# relay_dip_v02.net
KiCad netlist of a schematic drawn in EAGLE
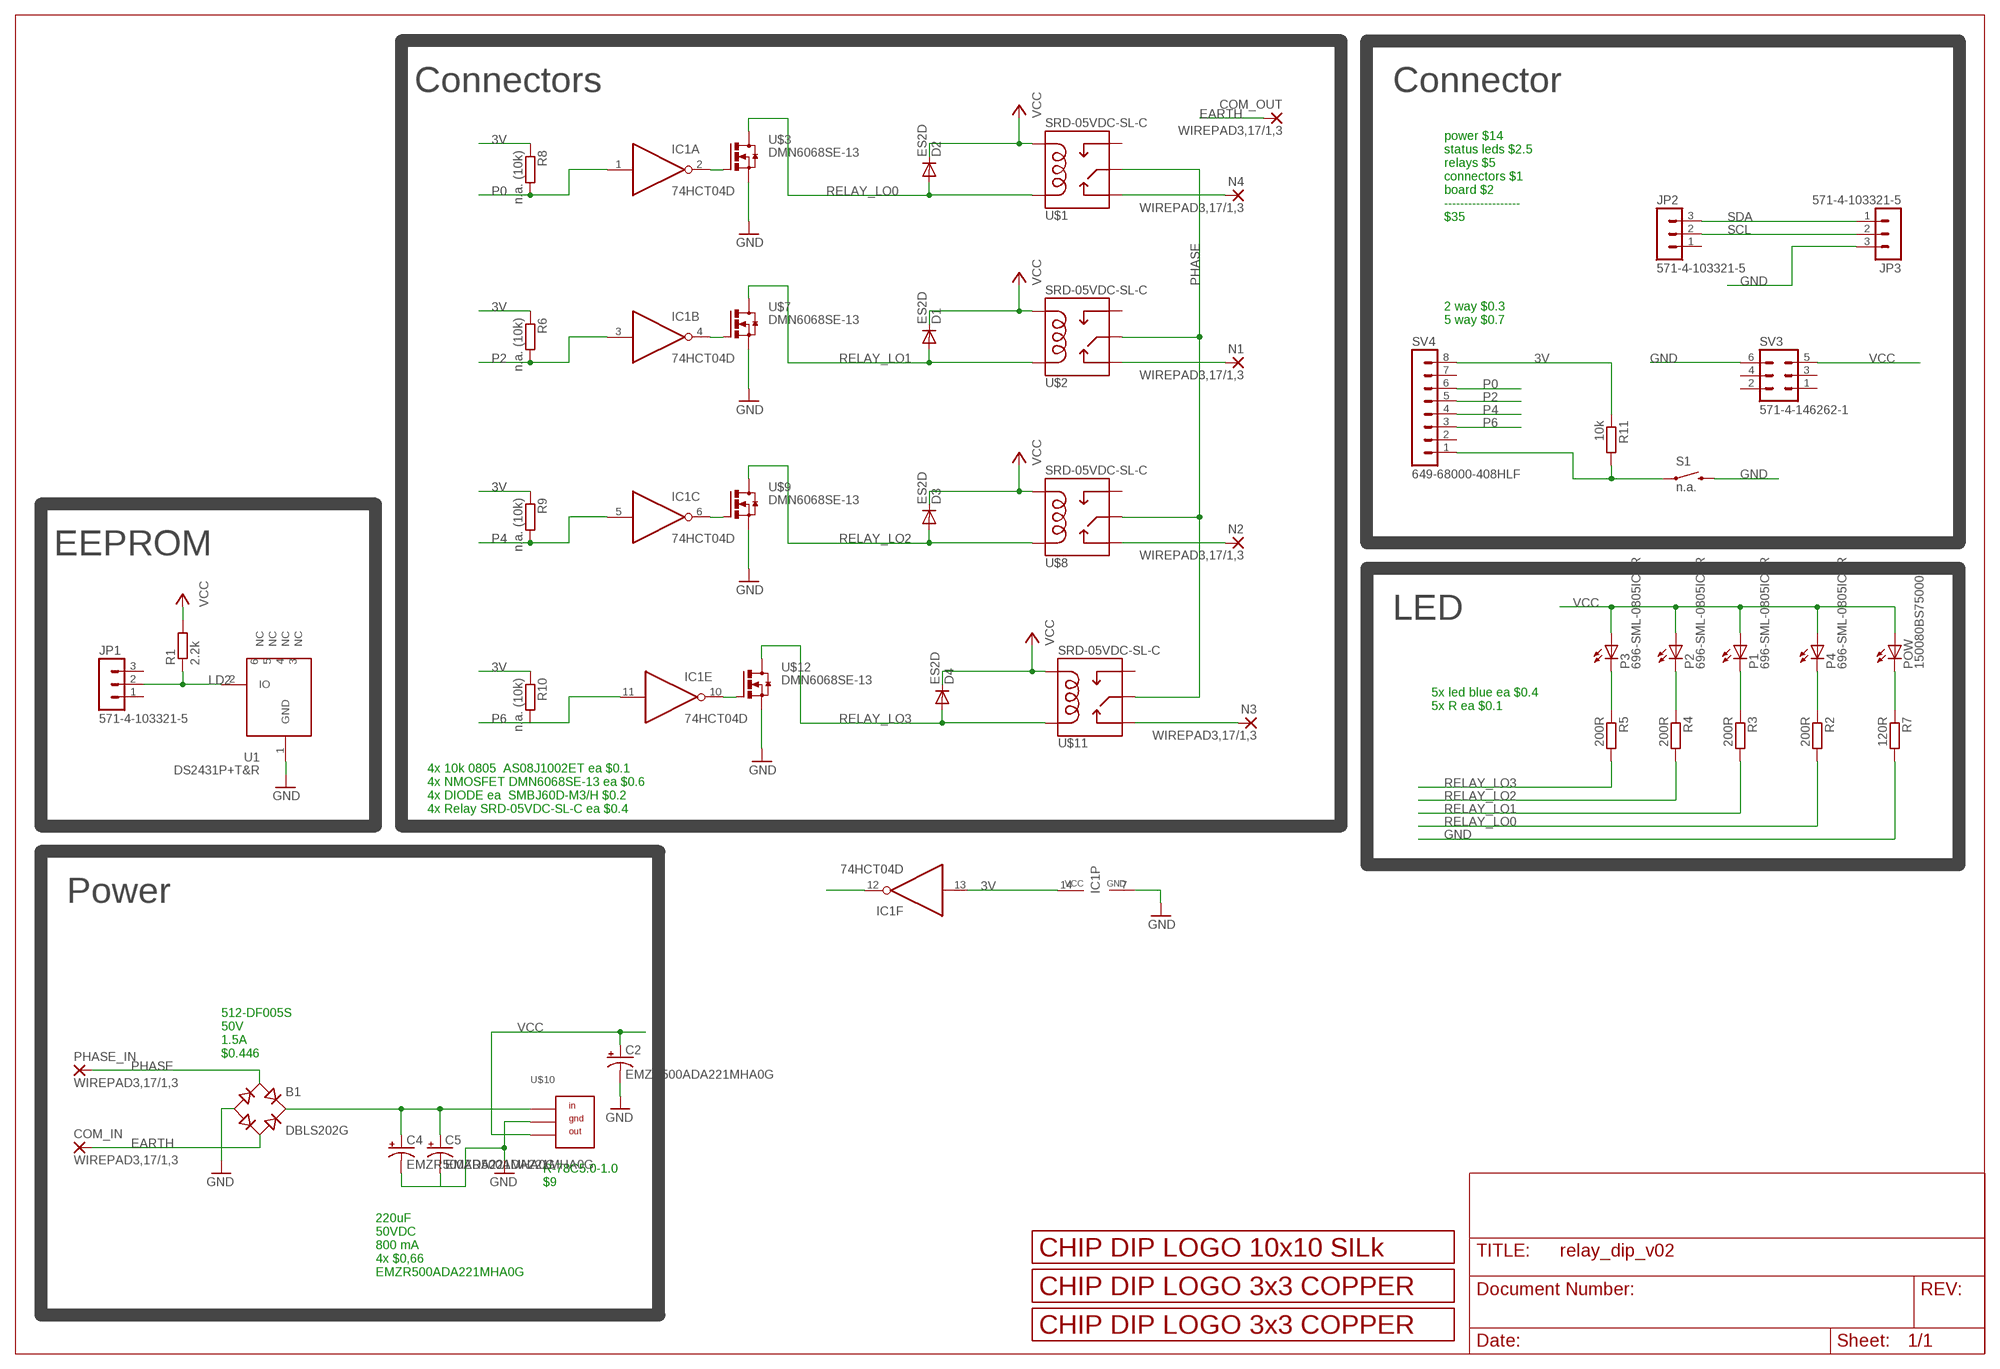
[diagram p0: schematic, sheet 1]

(export (version "E")
  (design (tool "Eeschema 10.0.6"))
  (components
    (comp (ref "B1")
      (value "DBLS202G")
      (footprint "eagle-import:DBS")
      (libsource (lib "eagle-import") (part "DB?GLS202"))
    )
    (comp (ref "C2")
      (value "EMZR500ADA221MHA0G")
      (footprint "eagle-import:150CLZ-0810")
      (libsource (lib "eagle-import") (part "CPOL-US150CLZ-0810"))
    )
    (comp (ref "C4")
      (value "EMZR500ADA221MHA0G")
      (footprint "eagle-import:150CLZ-0810")
      (libsource (lib "eagle-import") (part "CPOL-US150CLZ-0810"))
    )
    (comp (ref "C5")
      (value "EMZR500ADA221MHA0G")
      (footprint "eagle-import:150CLZ-0810")
      (libsource (lib "eagle-import") (part "CPOL-US150CLZ-0810"))
    )
    (comp (ref "COM_IN")
      (value "WIREPAD3,17/1,3")
      (footprint "eagle-import:3,17_1,3")
      (libsource (lib "eagle-import") (part "WIREPAD3,17/1,3"))
    )
    (comp (ref "COM_OUT")
      (value "WIREPAD3,17/1,3")
      (footprint "eagle-import:3,17_1,3")
      (libsource (lib "eagle-import") (part "WIREPAD3,17/1,3"))
    )
    (comp (ref "D1")
      (value "ES2D")
      (footprint "eagle-import:SMB")
      (libsource (lib "eagle-import") (part "DIODE-SMB"))
    )
    (comp (ref "D2")
      (value "ES2D")
      (footprint "eagle-import:SMB")
      (libsource (lib "eagle-import") (part "DIODE-SMB"))
    )
    (comp (ref "D3")
      (value "ES2D")
      (footprint "eagle-import:SMB")
      (libsource (lib "eagle-import") (part "DIODE-SMB"))
    )
    (comp (ref "D4")
      (value "ES2D")
      (footprint "eagle-import:SMB")
      (libsource (lib "eagle-import") (part "DIODE-SMB"))
    )
    (comp (ref "IC1")
      (value "74HCT04D")
      (footprint "eagle-import:SO14")
      (libsource (lib "eagle-import") (part "7404DHCT"))
    )
    (comp (ref "JP1")
      (value "571-4-103321-5")
      (footprint "eagle-import:MA03-1")
      (libsource (lib "eagle-import") (part "MA03-1"))
    )
    (comp (ref "JP2")
      (value "571-4-103321-5")
      (footprint "eagle-import:MA03-1")
      (libsource (lib "eagle-import") (part "MA03-1"))
    )
    (comp (ref "JP3")
      (value "571-4-103321-5")
      (footprint "eagle-import:MA03-1")
      (libsource (lib "eagle-import") (part "MA03-1"))
    )
    (comp (ref "N1")
      (value "WIREPAD3,17/1,3")
      (footprint "eagle-import:3,17_1,3")
      (libsource (lib "eagle-import") (part "WIREPAD3,17/1,3"))
    )
    (comp (ref "N2")
      (value "WIREPAD3,17/1,3")
      (footprint "eagle-import:3,17_1,3")
      (libsource (lib "eagle-import") (part "WIREPAD3,17/1,3"))
    )
    (comp (ref "N3")
      (value "WIREPAD3,17/1,3")
      (footprint "eagle-import:3,17_1,3")
      (libsource (lib "eagle-import") (part "WIREPAD3,17/1,3"))
    )
    (comp (ref "N4")
      (value "WIREPAD3,17/1,3")
      (footprint "eagle-import:3,17_1,3")
      (libsource (lib "eagle-import") (part "WIREPAD3,17/1,3"))
    )
    (comp (ref "P1")
      (value "696-SML-0805ICTR")
      (footprint "eagle-import:CHIP-LED0805")
      (libsource (lib "eagle-import") (part "LEDCHIP-LED0805"))
    )
    (comp (ref "P2")
      (value "696-SML-0805ICTR")
      (footprint "eagle-import:CHIP-LED0805")
      (libsource (lib "eagle-import") (part "LEDCHIP-LED0805"))
    )
    (comp (ref "P3")
      (value "696-SML-0805ICTR")
      (footprint "eagle-import:CHIP-LED0805")
      (libsource (lib "eagle-import") (part "LEDCHIP-LED0805"))
    )
    (comp (ref "P4")
      (value "696-SML-0805ICTR")
      (footprint "eagle-import:CHIP-LED0805")
      (libsource (lib "eagle-import") (part "LEDCHIP-LED0805"))
    )
    (comp (ref "PHASE_IN")
      (value "WIREPAD3,17/1,3")
      (footprint "eagle-import:3,17_1,3")
      (libsource (lib "eagle-import") (part "WIREPAD3,17/1,3"))
    )
    (comp (ref "POW")
      (value "150080BS75000")
      (footprint "eagle-import:CHIP-LED0805")
      (libsource (lib "eagle-import") (part "LEDCHIP-LED0805"))
    )
    (comp (ref "R1")
      (value "2.2k")
      (footprint "eagle-import:R0805")
      (libsource (lib "eagle-import") (part "R-EU_R0805"))
    )
    (comp (ref "R2")
      (value "200R")
      (footprint "eagle-import:R0805")
      (libsource (lib "eagle-import") (part "R-EU_R0805"))
    )
    (comp (ref "R3")
      (value "200R")
      (footprint "eagle-import:R0805")
      (libsource (lib "eagle-import") (part "R-EU_R0805"))
    )
    (comp (ref "R4")
      (value "200R")
      (footprint "eagle-import:R0805")
      (libsource (lib "eagle-import") (part "R-EU_R0805"))
    )
    (comp (ref "R5")
      (value "200R")
      (footprint "eagle-import:R0805")
      (libsource (lib "eagle-import") (part "R-EU_R0805"))
    )
    (comp (ref "R6")
      (value "n.a. (10k)")
      (footprint "eagle-import:R0805")
      (libsource (lib "eagle-import") (part "R-EU_R0805"))
    )
    (comp (ref "R7")
      (value "120R")
      (footprint "eagle-import:R0805")
      (libsource (lib "eagle-import") (part "R-EU_R0805"))
    )
    (comp (ref "R8")
      (value "n.a. (10k)")
      (footprint "eagle-import:R0805")
      (libsource (lib "eagle-import") (part "R-EU_R0805"))
    )
    (comp (ref "R9")
      (value "n.a. (10k)")
      (footprint "eagle-import:R0805")
      (libsource (lib "eagle-import") (part "R-EU_R0805"))
    )
    (comp (ref "R10")
      (value "n.a. (10k)")
      (footprint "eagle-import:R0805")
      (libsource (lib "eagle-import") (part "R-EU_R0805"))
    )
    (comp (ref "R11")
      (value "10k")
      (footprint "eagle-import:R0805")
      (libsource (lib "eagle-import") (part "R-EU_R0805"))
    )
    (comp (ref "S1")
      (value "n.a.")
      (footprint "eagle-import:TACTILE-SWITCH-SMD")
      (libsource (lib "eagle-import") (part "SWITCH-MOMENTARY-2SMD"))
    )
    (comp (ref "SV3")
      (value "571-4-146262-1")
      (footprint "eagle-import:MA03-2")
      (libsource (lib "eagle-import") (part "MA03-2"))
    )
    (comp (ref "SV4")
      (value "649-68000-408HLF")
      (footprint "eagle-import:MA08-1")
      (libsource (lib "eagle-import") (part "MA08-1"))
    )
    (comp (ref "U$1")
      (value "SRD-05VDC-SL-C")
      (footprint "eagle-import:SRD-05VDC-SL-C")
      (libsource (lib "eagle-import") (part "RELAYPTH"))
    )
    (comp (ref "U$2")
      (value "SRD-05VDC-SL-C")
      (footprint "eagle-import:SRD-05VDC-SL-C")
      (libsource (lib "eagle-import") (part "RELAYPTH"))
    )
    (comp (ref "U$3")
      (value "DMN6068SE-13")
      (footprint "eagle-import:SOT223")
      (libsource (lib "eagle-import") (part "NMOSFET_SMD_223"))
    )
    (comp (ref "U$4")
      (value "LOGO_3X3_COPPER")
      (footprint "eagle-import:LOGO_3X3_COPPER")
      (libsource (lib "eagle-import") (part "LOGO_3X3_COPPER"))
    )
    (comp (ref "U$5")
      (value "LOGO_10X10_SILK")
      (footprint "eagle-import:LOGO_10X10_SILK")
      (libsource (lib "eagle-import") (part "LOGO_10X10_SILK"))
    )
    (comp (ref "U$6")
      (value "LOGO_3X3_COPPER")
      (footprint "eagle-import:LOGO_3X3_COPPER")
      (libsource (lib "eagle-import") (part "LOGO_3X3_COPPER"))
    )
    (comp (ref "U$7")
      (value "DMN6068SE-13")
      (footprint "eagle-import:SOT223")
      (libsource (lib "eagle-import") (part "NMOSFET_SMD_223"))
    )
    (comp (ref "U$8")
      (value "SRD-05VDC-SL-C")
      (footprint "eagle-import:SRD-05VDC-SL-C")
      (libsource (lib "eagle-import") (part "RELAYPTH"))
    )
    (comp (ref "U$9")
      (value "DMN6068SE-13")
      (footprint "eagle-import:SOT223")
      (libsource (lib "eagle-import") (part "NMOSFET_SMD_223"))
    )
    (comp (ref "U$10")
      (value "R-7805-1.0")
      (footprint "eagle-import:SIP3")
      (libsource (lib "eagle-import") (part "R-7805-1.0"))
    )
    (comp (ref "U$11")
      (value "SRD-05VDC-SL-C")
      (footprint "eagle-import:SRD-05VDC-SL-C")
      (libsource (lib "eagle-import") (part "RELAYPTH"))
    )
    (comp (ref "U$12")
      (value "DMN6068SE-13")
      (footprint "eagle-import:SOT223")
      (libsource (lib "eagle-import") (part "NMOSFET_SMD_223"))
    )
    (comp (ref "U1")
      (value "DS2431P+T&R")
      (footprint "eagle-import:TSOC6")
      (fields (field (name "MFG") "DIGIKEY"))
      (libsource (lib "eagle-import") (part "DS2431P"))
    )
  )
  (nets
    (net (code "1") (name "/3V") (class "Default")
      (node (ref "IC1") (pin "13") (pinfunction "I_13") (pintype "input"))
      (node (ref "IC1") (pin "14") (pinfunction "VCC_14") (pintype "power_in"))
      (node (ref "R10") (pin "1") (pinfunction "1_1") (pintype "passive"))
      (node (ref "R11") (pin "1") (pinfunction "1_1") (pintype "passive"))
      (node (ref "R6") (pin "1") (pinfunction "1_1") (pintype "passive"))
      (node (ref "R8") (pin "1") (pinfunction "1_1") (pintype "passive"))
      (node (ref "R9") (pin "1") (pinfunction "1_1") (pintype "passive"))
      (node (ref "SV4") (pin "8") (pinfunction "8_8") (pintype "passive"))
    )
    (net (code "2") (name "/EARTH") (class "Default")
      (node (ref "B1") (pin "AC2") (pinfunction "AC2_AC2") (pintype "passive"))
      (node (ref "COM_IN") (pin "1") (pinfunction "P_1") (pintype "passive"))
      (node (ref "COM_OUT") (pin "1") (pinfunction "P_1") (pintype "passive"))
    )
    (net (code "3") (name "/LD2") (class "Default")
      (node (ref "JP1") (pin "2") (pinfunction "2_2") (pintype "passive"))
      (node (ref "R1") (pin "1") (pinfunction "1_1") (pintype "passive"))
      (node (ref "U1") (pin "2") (pinfunction "IO_2") (pintype "bidirectional"))
    )
    (net (code "4") (name "/P0") (class "Default")
      (node (ref "IC1") (pin "1") (pinfunction "I_1") (pintype "input"))
      (node (ref "R8") (pin "2") (pinfunction "2_2") (pintype "passive"))
      (node (ref "SV4") (pin "6") (pinfunction "6_6") (pintype "passive"))
    )
    (net (code "5") (name "/P2") (class "Default")
      (node (ref "IC1") (pin "3") (pinfunction "I_3") (pintype "input"))
      (node (ref "R6") (pin "2") (pinfunction "2_2") (pintype "passive"))
      (node (ref "SV4") (pin "5") (pinfunction "5_5") (pintype "passive"))
    )
    (net (code "6") (name "/P4") (class "Default")
      (node (ref "IC1") (pin "5") (pinfunction "I_5") (pintype "input"))
      (node (ref "R9") (pin "2") (pinfunction "2_2") (pintype "passive"))
      (node (ref "SV4") (pin "4") (pinfunction "4_4") (pintype "passive"))
    )
    (net (code "7") (name "/P6") (class "Default")
      (node (ref "IC1") (pin "11") (pinfunction "I_11") (pintype "input"))
      (node (ref "R10") (pin "2") (pinfunction "2_2") (pintype "passive"))
      (node (ref "SV4") (pin "3") (pinfunction "3_3") (pintype "passive"))
    )
    (net (code "8") (name "/PHASE") (class "Default")
      (node (ref "B1") (pin "AC1") (pinfunction "AC1_AC1") (pintype "passive"))
      (node (ref "PHASE_IN") (pin "1") (pinfunction "P_1") (pintype "passive"))
      (node (ref "U$1") (pin "SWCOMMON") (pinfunction "SWCOMMON_SWCOMMON") (pintype "bidirectional"))
      (node (ref "U$11") (pin "SWCOMMON") (pinfunction "SWCOMMON_SWCOMMON") (pintype "bidirectional"))
      (node (ref "U$2") (pin "SWCOMMON") (pinfunction "SWCOMMON_SWCOMMON") (pintype "bidirectional"))
      (node (ref "U$8") (pin "SWCOMMON") (pinfunction "SWCOMMON_SWCOMMON") (pintype "bidirectional"))
    )
    (net (code "9") (name "/RELAY_LO0") (class "Default")
      (node (ref "D2") (pin "A") (pinfunction "A_A") (pintype "passive"))
      (node (ref "R2") (pin "2") (pinfunction "2_2") (pintype "passive"))
      (node (ref "U$1") (pin "COIL1") (pinfunction "COIL1_COIL1") (pintype "bidirectional"))
      (node (ref "U$3") (pin "2") (pinfunction "D_2") (pintype "passive"))
      (node (ref "U$3") (pin "4") (pinfunction "D_4") (pintype "passive"))
    )
    (net (code "10") (name "/RELAY_LO1") (class "Default")
      (node (ref "D1") (pin "A") (pinfunction "A_A") (pintype "passive"))
      (node (ref "R3") (pin "2") (pinfunction "2_2") (pintype "passive"))
      (node (ref "U$2") (pin "COIL1") (pinfunction "COIL1_COIL1") (pintype "bidirectional"))
      (node (ref "U$7") (pin "2") (pinfunction "D_2") (pintype "passive"))
      (node (ref "U$7") (pin "4") (pinfunction "D_4") (pintype "passive"))
    )
    (net (code "11") (name "/RELAY_LO2") (class "Default")
      (node (ref "D3") (pin "A") (pinfunction "A_A") (pintype "passive"))
      (node (ref "R4") (pin "2") (pinfunction "2_2") (pintype "passive"))
      (node (ref "U$8") (pin "COIL1") (pinfunction "COIL1_COIL1") (pintype "bidirectional"))
      (node (ref "U$9") (pin "2") (pinfunction "D_2") (pintype "passive"))
      (node (ref "U$9") (pin "4") (pinfunction "D_4") (pintype "passive"))
    )
    (net (code "12") (name "/RELAY_LO3") (class "Default")
      (node (ref "D4") (pin "A") (pinfunction "A_A") (pintype "passive"))
      (node (ref "R5") (pin "2") (pinfunction "2_2") (pintype "passive"))
      (node (ref "U$11") (pin "COIL1") (pinfunction "COIL1_COIL1") (pintype "bidirectional"))
      (node (ref "U$12") (pin "2") (pinfunction "D_2") (pintype "passive"))
      (node (ref "U$12") (pin "4") (pinfunction "D_4") (pintype "passive"))
    )
    (net (code "13") (name "/SCL") (class "Default")
      (node (ref "JP2") (pin "2") (pinfunction "2_2") (pintype "passive"))
      (node (ref "JP3") (pin "2") (pinfunction "2_2") (pintype "passive"))
    )
    (net (code "14") (name "/SDA") (class "Default")
      (node (ref "JP2") (pin "3") (pinfunction "3_3") (pintype "passive"))
      (node (ref "JP3") (pin "1") (pinfunction "1_1") (pintype "passive"))
    )
    (net (code "15") (name "GND") (class "Default")
      (node (ref "B1") (pin "-") (pinfunction "-_-") (pintype "passive"))
      (node (ref "C2") (pin "-") (pinfunction "-_-") (pintype "passive"))
      (node (ref "C4") (pin "-") (pinfunction "-_-") (pintype "passive"))
      (node (ref "C5") (pin "-") (pinfunction "-_-") (pintype "passive"))
      (node (ref "IC1") (pin "7") (pinfunction "GND_7") (pintype "power_in"))
      (node (ref "JP3") (pin "3") (pinfunction "3_3") (pintype "passive"))
      (node (ref "R7") (pin "2") (pinfunction "2_2") (pintype "passive"))
      (node (ref "S1") (pin "3") (pinfunction "2_3") (pintype "passive"))
      (node (ref "SV3") (pin "6") (pinfunction "6_6") (pintype "passive"))
      (node (ref "U$10") (pin "GND") (pinfunction "GND_GND") (pintype "bidirectional"))
      (node (ref "U$12") (pin "3") (pinfunction "S_3") (pintype "passive"))
      (node (ref "U$3") (pin "3") (pinfunction "S_3") (pintype "passive"))
      (node (ref "U$7") (pin "3") (pinfunction "S_3") (pintype "passive"))
      (node (ref "U$9") (pin "3") (pinfunction "S_3") (pintype "passive"))
      (node (ref "U1") (pin "1") (pinfunction "GND_1") (pintype "bidirectional"))
    )
    (net (code "16") (name "Net-(B1-Pad+)") (class "Default")
      (node (ref "B1") (pin "+") (pinfunction "+_+") (pintype "passive"))
      (node (ref "C4") (pin "+") (pinfunction "+_+") (pintype "passive"))
      (node (ref "C5") (pin "+") (pinfunction "+_+") (pintype "passive"))
      (node (ref "U$10") (pin "IN") (pinfunction "IN_IN") (pintype "bidirectional"))
    )
    (net (code "17") (name "Net-(IC1A-O)") (class "Default")
      (node (ref "IC1") (pin "2") (pinfunction "O_2") (pintype "output"))
      (node (ref "U$3") (pin "1") (pinfunction "G_1") (pintype "passive"))
    )
    (net (code "18") (name "Net-(IC1B-O)") (class "Default")
      (node (ref "IC1") (pin "4") (pinfunction "O_4") (pintype "output"))
      (node (ref "U$7") (pin "1") (pinfunction "G_1") (pintype "passive"))
    )
    (net (code "19") (name "Net-(IC1C-O)") (class "Default")
      (node (ref "IC1") (pin "6") (pinfunction "O_6") (pintype "output"))
      (node (ref "U$9") (pin "1") (pinfunction "G_1") (pintype "passive"))
    )
    (net (code "20") (name "Net-(IC1E-O)") (class "Default")
      (node (ref "IC1") (pin "10") (pinfunction "O_10") (pintype "output"))
      (node (ref "U$12") (pin "1") (pinfunction "G_1") (pintype "passive"))
    )
    (net (code "21") (name "Net-(N1-P)") (class "Default")
      (node (ref "N1") (pin "1") (pinfunction "P_1") (pintype "passive"))
      (node (ref "U$2") (pin "SWCLOSED") (pinfunction "SWCLOSE_SWCLOSED") (pintype "bidirectional"))
    )
    (net (code "22") (name "Net-(N2-P)") (class "Default")
      (node (ref "N2") (pin "1") (pinfunction "P_1") (pintype "passive"))
      (node (ref "U$8") (pin "SWCLOSED") (pinfunction "SWCLOSE_SWCLOSED") (pintype "bidirectional"))
    )
    (net (code "23") (name "Net-(N3-P)") (class "Default")
      (node (ref "N3") (pin "1") (pinfunction "P_1") (pintype "passive"))
      (node (ref "U$11") (pin "SWCLOSED") (pinfunction "SWCLOSE_SWCLOSED") (pintype "bidirectional"))
    )
    (net (code "24") (name "Net-(N4-P)") (class "Default")
      (node (ref "N4") (pin "1") (pinfunction "P_1") (pintype "passive"))
      (node (ref "U$1") (pin "SWCLOSED") (pinfunction "SWCLOSE_SWCLOSED") (pintype "bidirectional"))
    )
    (net (code "25") (name "Net-(P1-PadC)") (class "Default")
      (node (ref "P1") (pin "C") (pinfunction "C_C") (pintype "passive"))
      (node (ref "R3") (pin "1") (pinfunction "1_1") (pintype "passive"))
    )
    (net (code "26") (name "Net-(P2-PadC)") (class "Default")
      (node (ref "P2") (pin "C") (pinfunction "C_C") (pintype "passive"))
      (node (ref "R4") (pin "1") (pinfunction "1_1") (pintype "passive"))
    )
    (net (code "27") (name "Net-(P3-PadC)") (class "Default")
      (node (ref "P3") (pin "C") (pinfunction "C_C") (pintype "passive"))
      (node (ref "R5") (pin "1") (pinfunction "1_1") (pintype "passive"))
    )
    (net (code "28") (name "Net-(P4-PadC)") (class "Default")
      (node (ref "P4") (pin "C") (pinfunction "C_C") (pintype "passive"))
      (node (ref "R2") (pin "1") (pinfunction "1_1") (pintype "passive"))
    )
    (net (code "29") (name "Net-(POW-PadC)") (class "Default")
      (node (ref "POW") (pin "C") (pinfunction "C_C") (pintype "passive"))
      (node (ref "R7") (pin "1") (pinfunction "1_1") (pintype "passive"))
    )
    (net (code "30") (name "Net-(R11-Pad2)") (class "Default")
      (node (ref "R11") (pin "2") (pinfunction "2_2") (pintype "passive"))
      (node (ref "S1") (pin "1") (pinfunction "1_1") (pintype "passive"))
      (node (ref "SV4") (pin "1") (pinfunction "1_1") (pintype "passive"))
    )
    (net (code "31") (name "VCC") (class "Default")
      (node (ref "C2") (pin "+") (pinfunction "+_+") (pintype "passive"))
      (node (ref "D1") (pin "C") (pinfunction "C_C") (pintype "passive"))
      (node (ref "D2") (pin "C") (pinfunction "C_C") (pintype "passive"))
      (node (ref "D3") (pin "C") (pinfunction "C_C") (pintype "passive"))
      (node (ref "D4") (pin "C") (pinfunction "C_C") (pintype "passive"))
      (node (ref "P1") (pin "A") (pinfunction "A_A") (pintype "passive"))
      (node (ref "P2") (pin "A") (pinfunction "A_A") (pintype "passive"))
      (node (ref "P3") (pin "A") (pinfunction "A_A") (pintype "passive"))
      (node (ref "P4") (pin "A") (pinfunction "A_A") (pintype "passive"))
      (node (ref "POW") (pin "A") (pinfunction "A_A") (pintype "passive"))
      (node (ref "R1") (pin "2") (pinfunction "2_2") (pintype "passive"))
      (node (ref "SV3") (pin "5") (pinfunction "5_5") (pintype "passive"))
      (node (ref "U$1") (pin "COIL0") (pinfunction "COIL0_COIL0") (pintype "bidirectional"))
      (node (ref "U$10") (pin "OUT") (pinfunction "OUT_OUT") (pintype "bidirectional"))
      (node (ref "U$11") (pin "COIL0") (pinfunction "COIL0_COIL0") (pintype "bidirectional"))
      (node (ref "U$2") (pin "COIL0") (pinfunction "COIL0_COIL0") (pintype "bidirectional"))
      (node (ref "U$8") (pin "COIL0") (pinfunction "COIL0_COIL0") (pintype "bidirectional"))
    )
    (net (code "32") (name "unconnected-(IC1F-O-Pad12)") (class "Default")
      (node (ref "IC1") (pin "12") (pinfunction "O_12") (pintype "output"))
    )
    (net (code "33") (name "unconnected-(JP1-Pad1)") (class "Default")
      (node (ref "JP1") (pin "1") (pinfunction "1_1") (pintype "passive"))
    )
    (net (code "34") (name "unconnected-(JP1-Pad3)") (class "Default")
      (node (ref "JP1") (pin "3") (pinfunction "3_3") (pintype "passive"))
    )
    (net (code "35") (name "unconnected-(JP2-Pad1)") (class "Default")
      (node (ref "JP2") (pin "1") (pinfunction "1_1") (pintype "passive"))
    )
    (net (code "36") (name "unconnected-(SV3-Pad1)") (class "Default")
      (node (ref "SV3") (pin "1") (pinfunction "1_1") (pintype "passive"))
    )
    (net (code "37") (name "unconnected-(SV3-Pad2)") (class "Default")
      (node (ref "SV3") (pin "2") (pinfunction "2_2") (pintype "passive"))
    )
    (net (code "38") (name "unconnected-(SV3-Pad3)") (class "Default")
      (node (ref "SV3") (pin "3") (pinfunction "3_3") (pintype "passive"))
    )
    (net (code "39") (name "unconnected-(SV3-Pad4)") (class "Default")
      (node (ref "SV3") (pin "4") (pinfunction "4_4") (pintype "passive"))
    )
    (net (code "40") (name "unconnected-(SV4-Pad2)") (class "Default")
      (node (ref "SV4") (pin "2") (pinfunction "2_2") (pintype "passive"))
    )
    (net (code "41") (name "unconnected-(SV4-Pad7)") (class "Default")
      (node (ref "SV4") (pin "7") (pinfunction "7_7") (pintype "passive"))
    )
    (net (code "42") (name "unconnected-(U$1-PadSWOPEN)") (class "Default")
      (node (ref "U$1") (pin "SWOPEN") (pinfunction "SWOPEN_SWOPEN") (pintype "bidirectional"))
    )
    (net (code "43") (name "unconnected-(U$2-PadSWOPEN)") (class "Default")
      (node (ref "U$2") (pin "SWOPEN") (pinfunction "SWOPEN_SWOPEN") (pintype "bidirectional"))
    )
    (net (code "44") (name "unconnected-(U$8-PadSWOPEN)") (class "Default")
      (node (ref "U$8") (pin "SWOPEN") (pinfunction "SWOPEN_SWOPEN") (pintype "bidirectional"))
    )
    (net (code "45") (name "unconnected-(U$11-PadSWOPEN)") (class "Default")
      (node (ref "U$11") (pin "SWOPEN") (pinfunction "SWOPEN_SWOPEN") (pintype "bidirectional"))
    )
    (net (code "46") (name "unconnected-(U1-NC-Pad3)") (class "Default")
      (node (ref "U1") (pin "3") (pinfunction "NC_3") (pintype "bidirectional"))
    )
    (net (code "47") (name "unconnected-(U1-NC-Pad4)") (class "Default")
      (node (ref "U1") (pin "4") (pinfunction "NC_4") (pintype "bidirectional"))
    )
    (net (code "48") (name "unconnected-(U1-NC-Pad5)") (class "Default")
      (node (ref "U1") (pin "5") (pinfunction "NC_5") (pintype "bidirectional"))
    )
    (net (code "49") (name "unconnected-(U1-NC-Pad6)") (class "Default")
      (node (ref "U1") (pin "6") (pinfunction "NC_6") (pintype "bidirectional"))
    )
  )
)
